# tennisfortwof303.net
KiCad netlist of a schematic drawn in EAGLE
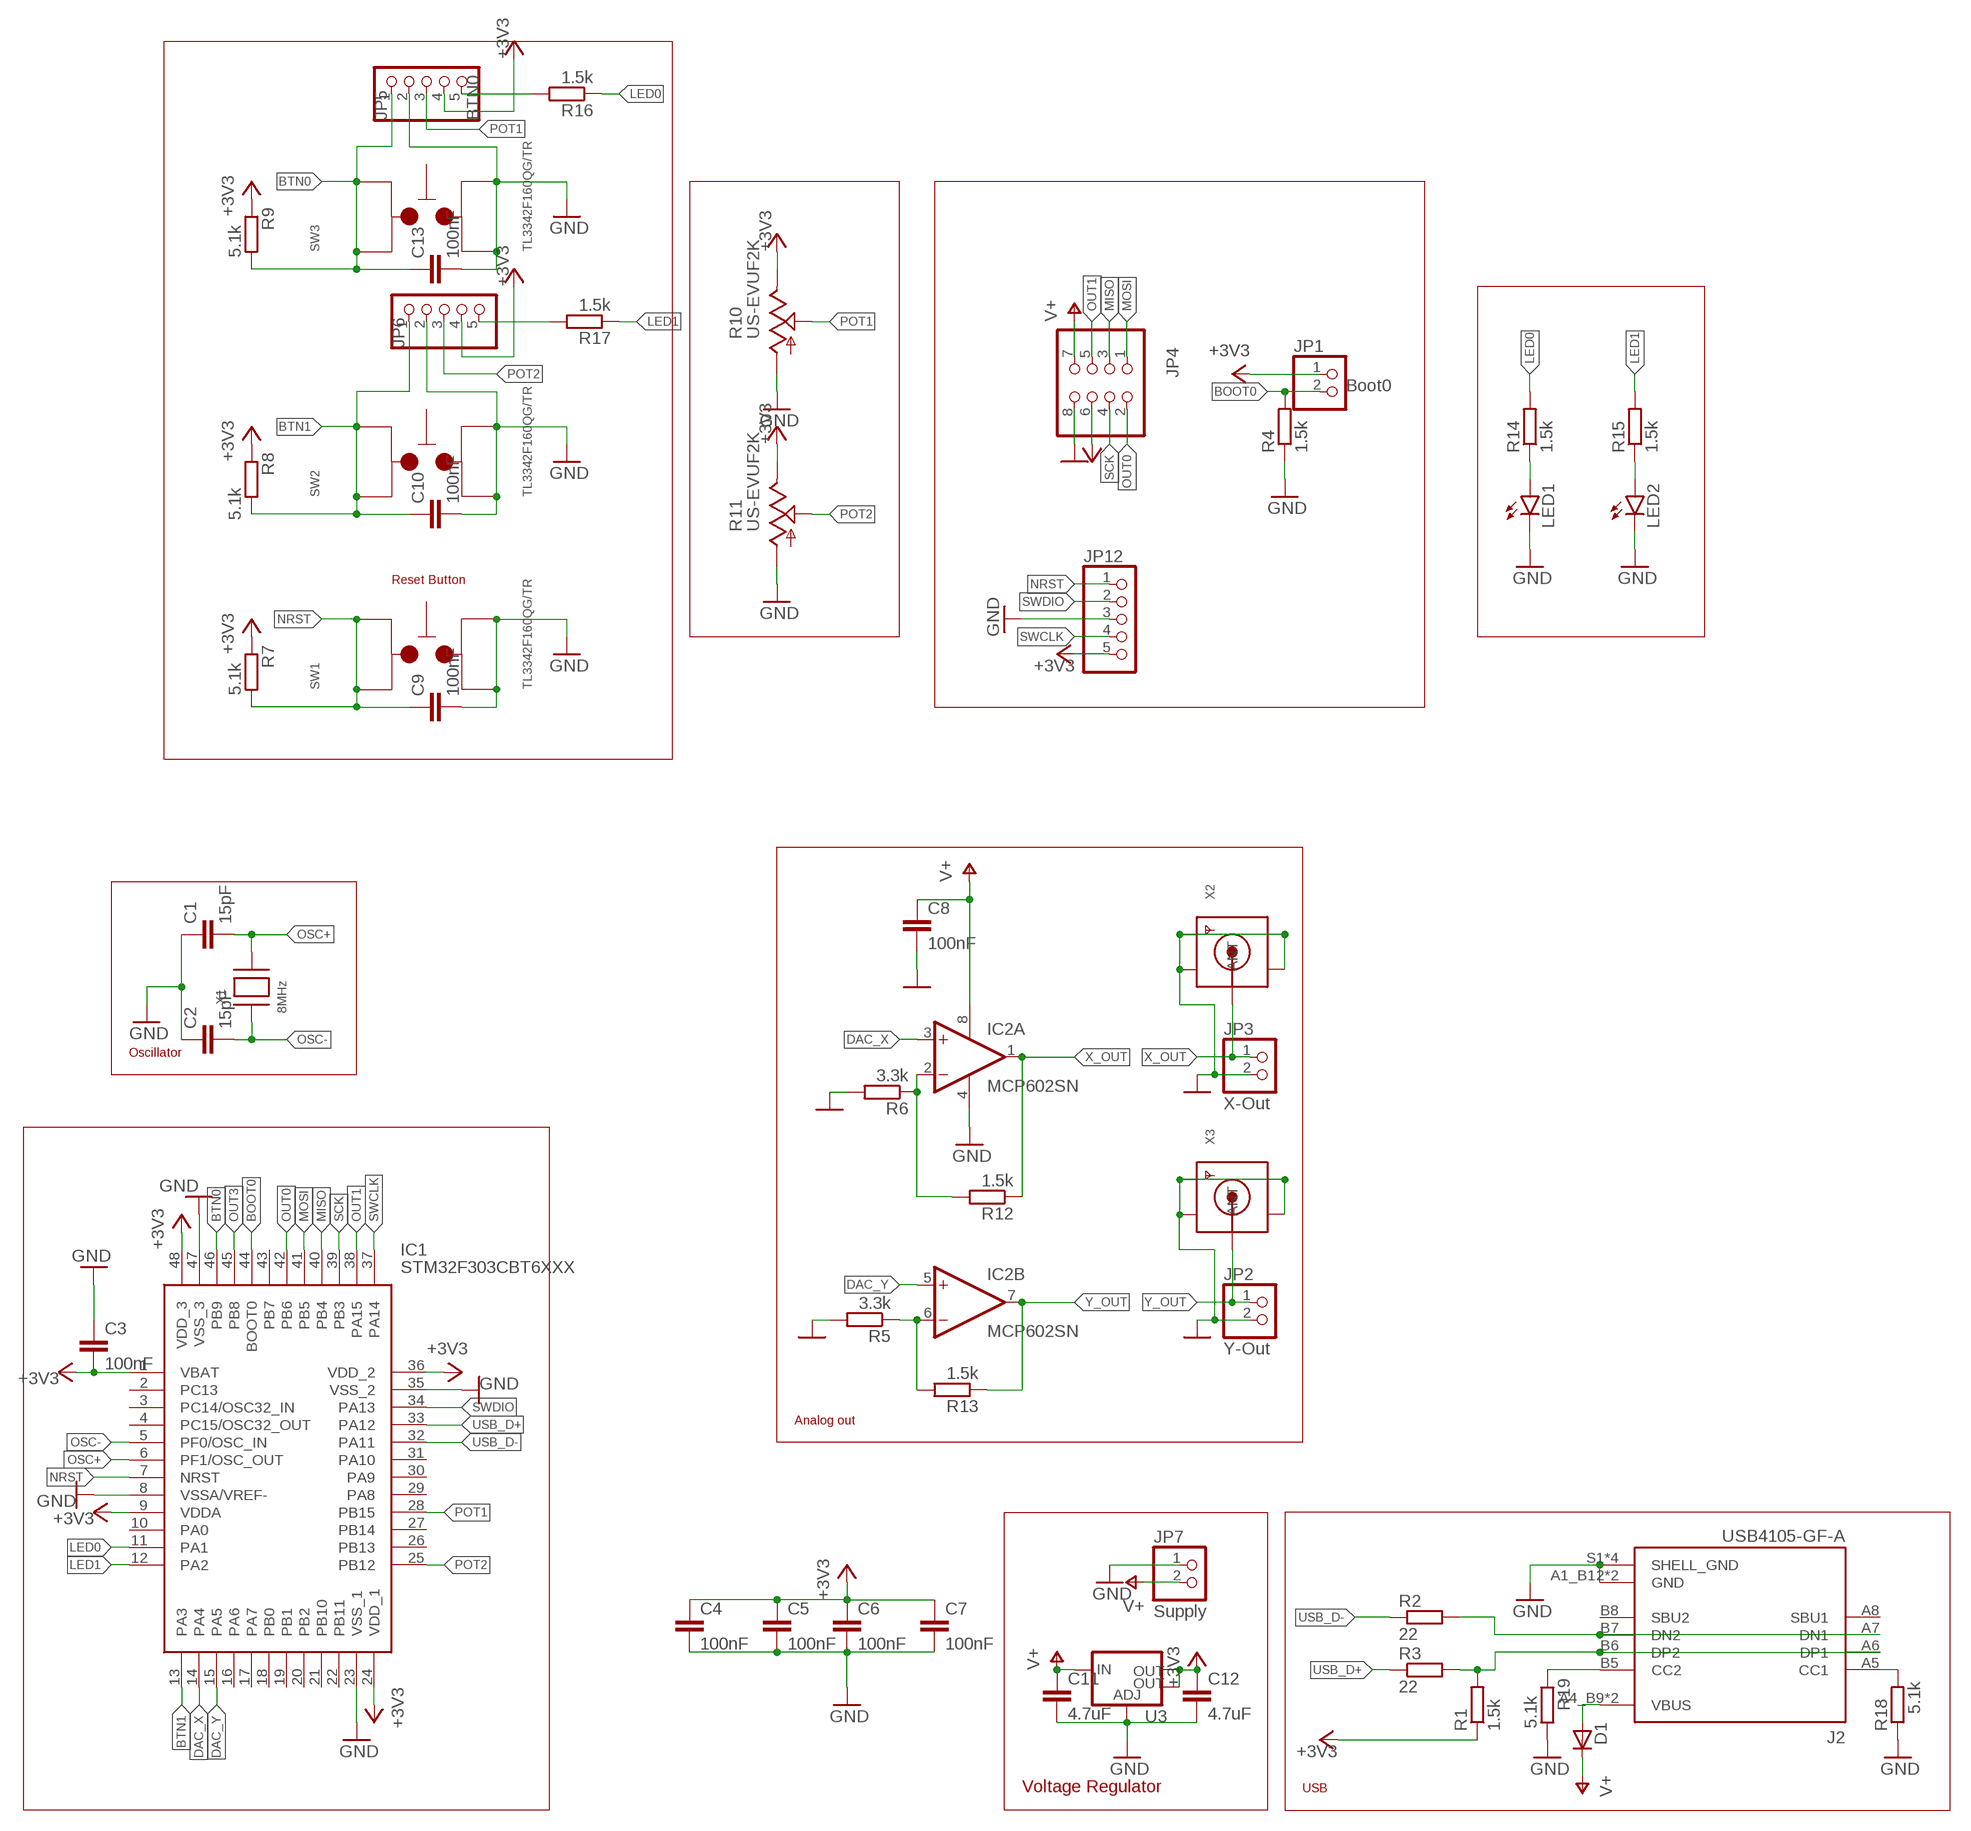
[diagram p0: schematic, sheet 1]

(export (version "E")
  (design (tool "Eeschema 10.0.6"))
  (components
    (comp (ref "C1")
      (value "15pF")
      (footprint "eagle-import:C0603")
      (libsource (lib "eagle-import") (part "C-EUC0603"))
    )
    (comp (ref "C2")
      (value "15pF")
      (footprint "eagle-import:C0603")
      (libsource (lib "eagle-import") (part "C-EUC0603"))
    )
    (comp (ref "C3")
      (value "100nF")
      (footprint "eagle-import:C0603")
      (libsource (lib "eagle-import") (part "C-EUC0603"))
    )
    (comp (ref "C4")
      (value "100nF")
      (footprint "eagle-import:C0603")
      (libsource (lib "eagle-import") (part "C-EUC0603"))
    )
    (comp (ref "C5")
      (value "100nF")
      (footprint "eagle-import:C0603")
      (libsource (lib "eagle-import") (part "C-EUC0603"))
    )
    (comp (ref "C6")
      (value "100nF")
      (footprint "eagle-import:C0603")
      (libsource (lib "eagle-import") (part "C-EUC0603"))
    )
    (comp (ref "C7")
      (value "100nF")
      (footprint "eagle-import:C0603")
      (libsource (lib "eagle-import") (part "C-EUC0603"))
    )
    (comp (ref "C8")
      (value "100nF")
      (footprint "eagle-import:C0603")
      (libsource (lib "eagle-import") (part "C-EUC0603"))
    )
    (comp (ref "C9")
      (value "100nF")
      (footprint "eagle-import:C0603")
      (libsource (lib "eagle-import") (part "C-EUC0603"))
    )
    (comp (ref "C10")
      (value "100nF")
      (footprint "eagle-import:C0603")
      (libsource (lib "eagle-import") (part "C-EUC0603"))
    )
    (comp (ref "C11")
      (value "4.7uF")
      (footprint "eagle-import:C0805")
      (libsource (lib "eagle-import") (part "C-EUC0805"))
    )
    (comp (ref "C12")
      (value "4.7uF")
      (footprint "eagle-import:C0805")
      (libsource (lib "eagle-import") (part "C-EUC0805"))
    )
    (comp (ref "C13")
      (value "100nF")
      (footprint "eagle-import:C0603")
      (libsource (lib "eagle-import") (part "C-EUC0603"))
    )
    (comp (ref "D1")
      (value "DIODESMA")
      (footprint "eagle-import:SMADIODE")
      (libsource (lib "eagle-import") (part "DIODESMA"))
    )
    (comp (ref "IC1")
      (value "STM32F303CBT6XXX")
      (footprint "eagle-import:QFP50P900X900X160-48N")
      (libsource (lib "eagle-import") (part "STM32F303CBT6XXX"))
    )
    (comp (ref "IC2")
      (value "MCP602SN")
      (footprint "eagle-import:SO08")
      (libsource (lib "eagle-import") (part "MCP602SN"))
    )
    (comp (ref "J2")
      (value "USB4105-GF-A")
      (footprint "eagle-import:GCT_USB4105-GF-A")
      (fields (field (name "MF") "GCT"))
      (libsource (lib "eagle-import") (part "USB4105-GF-A"))
    )
    (comp (ref "JP1")
      (value "Boot0")
      (footprint "eagle-import:1X02")
      (libsource (lib "eagle-import") (part "PINHD-1X2"))
    )
    (comp (ref "JP2")
      (value "Y-Out")
      (footprint "eagle-import:1X02")
      (libsource (lib "eagle-import") (part "PINHD-1X2"))
    )
    (comp (ref "JP3")
      (value "X-Out")
      (footprint "eagle-import:1X02")
      (libsource (lib "eagle-import") (part "PINHD-1X2"))
    )
    (comp (ref "JP4")
      (value "PINHD-2X4")
      (footprint "eagle-import:2X04")
      (libsource (lib "eagle-import") (part "PINHD-2X4"))
    )
    (comp (ref "JP5")
      (value "BTN0")
      (footprint "eagle-import:1X05_90")
      (libsource (lib "eagle-import") (part "PINHD-1X5/90"))
    )
    (comp (ref "JP6")
      (value "BTN1")
      (footprint "eagle-import:1X05_90")
      (libsource (lib "eagle-import") (part "PINHD-1X5/90"))
    )
    (comp (ref "JP7")
      (value "Supply")
      (footprint "eagle-import:1X02")
      (libsource (lib "eagle-import") (part "PINHD-1X2"))
    )
    (comp (ref "JP12")
      (value "PINHD-1X5")
      (footprint "eagle-import:1X05")
      (libsource (lib "eagle-import") (part "PINHD-1X5"))
    )
    (comp (ref "LED1")
      (value "LEDCHIPLED_0805")
      (footprint "eagle-import:CHIPLED_0805")
      (libsource (lib "eagle-import") (part "LEDCHIPLED_0805"))
    )
    (comp (ref "LED2")
      (value "LEDCHIPLED_0805")
      (footprint "eagle-import:CHIPLED_0805")
      (libsource (lib "eagle-import") (part "LEDCHIPLED_0805"))
    )
    (comp (ref "R1")
      (value "1.5k")
      (footprint "eagle-import:R0603")
      (libsource (lib "eagle-import") (part "R-EU_R0603"))
    )
    (comp (ref "R2")
      (value "22")
      (footprint "eagle-import:R0603")
      (libsource (lib "eagle-import") (part "R-EU_R0603"))
    )
    (comp (ref "R3")
      (value "22")
      (footprint "eagle-import:R0603")
      (libsource (lib "eagle-import") (part "R-EU_R0603"))
    )
    (comp (ref "R4")
      (value "1.5k")
      (footprint "eagle-import:R0603")
      (libsource (lib "eagle-import") (part "R-EU_R0603"))
    )
    (comp (ref "R5")
      (value "3.3k")
      (footprint "eagle-import:R0603")
      (libsource (lib "eagle-import") (part "R-EU_R0603"))
    )
    (comp (ref "R6")
      (value "3.3k")
      (footprint "eagle-import:R0603")
      (libsource (lib "eagle-import") (part "R-EU_R0603"))
    )
    (comp (ref "R7")
      (value "5.1k")
      (footprint "eagle-import:R0603")
      (libsource (lib "eagle-import") (part "R-EU_R0603"))
    )
    (comp (ref "R8")
      (value "5.1k")
      (footprint "eagle-import:R0603")
      (libsource (lib "eagle-import") (part "R-EU_R0603"))
    )
    (comp (ref "R9")
      (value "5.1k")
      (footprint "eagle-import:R0603")
      (libsource (lib "eagle-import") (part "R-EU_R0603"))
    )
    (comp (ref "R10")
      (value "US-EVUF2K")
      (footprint "eagle-import:EVUFXK")
      (libsource (lib "eagle-import") (part "US-EVUF2K"))
    )
    (comp (ref "R11")
      (value "US-EVUF2K")
      (footprint "eagle-import:EVUFXK")
      (libsource (lib "eagle-import") (part "US-EVUF2K"))
    )
    (comp (ref "R12")
      (value "1.5k")
      (footprint "eagle-import:R0603")
      (libsource (lib "eagle-import") (part "R-EU_R0603"))
    )
    (comp (ref "R13")
      (value "1.5k")
      (footprint "eagle-import:R0603")
      (libsource (lib "eagle-import") (part "R-EU_R0603"))
    )
    (comp (ref "R14")
      (value "1.5k")
      (footprint "eagle-import:R0603")
      (libsource (lib "eagle-import") (part "R-EU_R0603"))
    )
    (comp (ref "R15")
      (value "1.5k")
      (footprint "eagle-import:R0603")
      (libsource (lib "eagle-import") (part "R-EU_R0603"))
    )
    (comp (ref "R16")
      (value "1.5k")
      (footprint "eagle-import:R0603")
      (libsource (lib "eagle-import") (part "R-EU_R0603"))
    )
    (comp (ref "R17")
      (value "1.5k")
      (footprint "eagle-import:R0603")
      (libsource (lib "eagle-import") (part "R-EU_R0603"))
    )
    (comp (ref "R18")
      (value "5.1k")
      (footprint "eagle-import:R0603")
      (libsource (lib "eagle-import") (part "R-EU_R0603"))
    )
    (comp (ref "R19")
      (value "5.1k")
      (footprint "eagle-import:R0603")
      (libsource (lib "eagle-import") (part "R-EU_R0603"))
    )
    (comp (ref "SW1")
      (value "TL3342F160QG/TR")
      (footprint "eagle-import:TL3342F160QG_TR")
      (fields
        (field (name "DIGI_KEY_PART_NUMBER") "EG2531CT-ND")
        (field (name "MANUFACTURER") "E-Switch")
        (field (name "CREATED_BY") "PCBLayout.com")
      )
      (libsource (lib "eagle-import") (part "TL3342F160QG/TR"))
    )
    (comp (ref "SW2")
      (value "TL3342F160QG/TR")
      (footprint "eagle-import:TL3342F160QG_TR")
      (fields
        (field (name "DIGI_KEY_PART_NUMBER") "EG2531CT-ND")
        (field (name "MANUFACTURER") "E-Switch")
        (field (name "CREATED_BY") "PCBLayout.com")
      )
      (libsource (lib "eagle-import") (part "TL3342F160QG/TR"))
    )
    (comp (ref "SW3")
      (value "TL3342F160QG/TR")
      (footprint "eagle-import:TL3342F160QG_TR")
      (fields
        (field (name "DIGI_KEY_PART_NUMBER") "EG2531CT-ND")
        (field (name "MANUFACTURER") "E-Switch")
        (field (name "CREATED_BY") "PCBLayout.com")
      )
      (libsource (lib "eagle-import") (part "TL3342F160QG/TR"))
    )
    (comp (ref "U3")
      (value "V_REG_LM1117SOT223")
      (footprint "eagle-import:SOT223")
      (libsource (lib "eagle-import") (part "V_REG_LM1117SOT223"))
    )
    (comp (ref "X1")
      (value "8MHz")
      (footprint "eagle-import:NX5032")
      (libsource (lib "eagle-import") (part "XTALNX5032"))
    )
    (comp (ref "X2")
      (value "SMACONNECTOR_EDGE")
      (footprint "eagle-import:SMA_EDGELAUNCH")
      (libsource (lib "eagle-import") (part "SMACONNECTOR_EDGE"))
    )
    (comp (ref "X3")
      (value "SMACONNECTOR_EDGE")
      (footprint "eagle-import:SMA_EDGELAUNCH")
      (libsource (lib "eagle-import") (part "SMACONNECTOR_EDGE"))
    )
  )
  (nets
    (net (code "1") (name "+3V3") (class "Default")
      (node (ref "C12") (pin "1") (pinfunction "1_1") (pintype "passive"))
      (node (ref "C3") (pin "2") (pinfunction "2_2") (pintype "passive"))
      (node (ref "C4") (pin "1") (pinfunction "1_1") (pintype "passive"))
      (node (ref "C5") (pin "1") (pinfunction "1_1") (pintype "passive"))
      (node (ref "C6") (pin "1") (pinfunction "1_1") (pintype "passive"))
      (node (ref "C7") (pin "1") (pinfunction "1_1") (pintype "passive"))
      (node (ref "IC1") (pin "1") (pinfunction "VBAT_1") (pintype "bidirectional"))
      (node (ref "IC1") (pin "24") (pinfunction "VDD_1_24") (pintype "bidirectional"))
      (node (ref "IC1") (pin "36") (pinfunction "VDD_2_36") (pintype "bidirectional"))
      (node (ref "IC1") (pin "48") (pinfunction "VDD_3_48") (pintype "bidirectional"))
      (node (ref "IC1") (pin "9") (pinfunction "VDDA_9") (pintype "bidirectional"))
      (node (ref "JP1") (pin "1") (pinfunction "1_1") (pintype "passive"))
      (node (ref "JP12") (pin "5") (pinfunction "5_5") (pintype "passive"))
      (node (ref "JP4") (pin "6") (pinfunction "6_6") (pintype "passive"))
      (node (ref "JP5") (pin "4") (pinfunction "4_4") (pintype "passive"))
      (node (ref "JP6") (pin "4") (pinfunction "4_4") (pintype "passive"))
      (node (ref "R1") (pin "1") (pinfunction "1_1") (pintype "passive"))
      (node (ref "R10") (pin "3") (pinfunction "E_3") (pintype "passive"))
      (node (ref "R11") (pin "3") (pinfunction "E_3") (pintype "passive"))
      (node (ref "R7") (pin "1") (pinfunction "1_1") (pintype "passive"))
      (node (ref "R8") (pin "1") (pinfunction "1_1") (pintype "passive"))
      (node (ref "R9") (pin "1") (pinfunction "1_1") (pintype "passive"))
      (node (ref "U3") (pin "2") (pinfunction "OUT_2") (pintype "output"))
      (node (ref "U3") (pin "4") (pinfunction "OUT_4") (pintype "output"))
    )
    (net (code "2") (name "BOOT0") (class "Default")
      (node (ref "IC1") (pin "44") (pinfunction "BOOT0_44") (pintype "bidirectional"))
      (node (ref "JP1") (pin "2") (pinfunction "2_2") (pintype "passive"))
      (node (ref "R4") (pin "2") (pinfunction "2_2") (pintype "passive"))
    )
    (net (code "3") (name "BTN0") (class "Default")
      (node (ref "C13") (pin "1") (pinfunction "1_1") (pintype "passive"))
      (node (ref "IC1") (pin "46") (pinfunction "PB9_46") (pintype "bidirectional"))
      (node (ref "JP5") (pin "1") (pinfunction "1_1") (pintype "passive"))
      (node (ref "R9") (pin "2") (pinfunction "2_2") (pintype "passive"))
      (node (ref "SW3") (pin "3") (pinfunction "3_3") (pintype "passive"))
      (node (ref "SW3") (pin "4") (pinfunction "4_4") (pintype "passive"))
    )
    (net (code "4") (name "BTN1") (class "Default")
      (node (ref "C10") (pin "1") (pinfunction "1_1") (pintype "passive"))
      (node (ref "IC1") (pin "13") (pinfunction "PA3_13") (pintype "bidirectional"))
      (node (ref "JP6") (pin "1") (pinfunction "1_1") (pintype "passive"))
      (node (ref "R8") (pin "2") (pinfunction "2_2") (pintype "passive"))
      (node (ref "SW2") (pin "3") (pinfunction "3_3") (pintype "passive"))
      (node (ref "SW2") (pin "4") (pinfunction "4_4") (pintype "passive"))
    )
    (net (code "5") (name "DAC_X") (class "Default")
      (node (ref "IC1") (pin "14") (pinfunction "PA4_14") (pintype "bidirectional"))
      (node (ref "IC2") (pin "3") (pinfunction "+IN_3") (pintype "input"))
    )
    (net (code "6") (name "DAC_Y") (class "Default")
      (node (ref "IC1") (pin "15") (pinfunction "PA5_15") (pintype "bidirectional"))
      (node (ref "IC2") (pin "5") (pinfunction "+IN_5") (pintype "input"))
    )
    (net (code "7") (name "GND") (class "Default")
      (node (ref "C1") (pin "1") (pinfunction "1_1") (pintype "passive"))
      (node (ref "C10") (pin "2") (pinfunction "2_2") (pintype "passive"))
      (node (ref "C11") (pin "2") (pinfunction "2_2") (pintype "passive"))
      (node (ref "C12") (pin "2") (pinfunction "2_2") (pintype "passive"))
      (node (ref "C13") (pin "2") (pinfunction "2_2") (pintype "passive"))
      (node (ref "C2") (pin "1") (pinfunction "1_1") (pintype "passive"))
      (node (ref "C3") (pin "1") (pinfunction "1_1") (pintype "passive"))
      (node (ref "C4") (pin "2") (pinfunction "2_2") (pintype "passive"))
      (node (ref "C5") (pin "2") (pinfunction "2_2") (pintype "passive"))
      (node (ref "C6") (pin "2") (pinfunction "2_2") (pintype "passive"))
      (node (ref "C7") (pin "2") (pinfunction "2_2") (pintype "passive"))
      (node (ref "C8") (pin "2") (pinfunction "2_2") (pintype "passive"))
      (node (ref "C9") (pin "2") (pinfunction "2_2") (pintype "passive"))
      (node (ref "IC1") (pin "23") (pinfunction "VSS_1_23") (pintype "bidirectional"))
      (node (ref "IC1") (pin "35") (pinfunction "VSS_2_35") (pintype "bidirectional"))
      (node (ref "IC1") (pin "47") (pinfunction "VSS_3_47") (pintype "bidirectional"))
      (node (ref "IC1") (pin "8") (pinfunction "VSSA/VREF-_8") (pintype "bidirectional"))
      (node (ref "IC2") (pin "4") (pinfunction "V-_4") (pintype "power_in"))
      (node (ref "J2") (pin "A1_B12") (pinfunction "GND_A1_B12") (pintype "power_in"))
      (node (ref "J2") (pin "B1_A12") (pinfunction "GND_B1_A12") (pintype "power_in"))
      (node (ref "J2") (pin "S1") (pinfunction "SHELL_GND_S1") (pintype "power_in"))
      (node (ref "J2") (pin "S2") (pinfunction "SHELL_GND_S2") (pintype "power_in"))
      (node (ref "J2") (pin "S3") (pinfunction "SHELL_GND_S3") (pintype "power_in"))
      (node (ref "J2") (pin "S4") (pinfunction "SHELL_GND_S4") (pintype "power_in"))
      (node (ref "JP12") (pin "3") (pinfunction "3_3") (pintype "passive"))
      (node (ref "JP2") (pin "2") (pinfunction "2_2") (pintype "passive"))
      (node (ref "JP3") (pin "2") (pinfunction "2_2") (pintype "passive"))
      (node (ref "JP4") (pin "8") (pinfunction "8_8") (pintype "passive"))
      (node (ref "JP5") (pin "2") (pinfunction "2_2") (pintype "passive"))
      (node (ref "JP6") (pin "2") (pinfunction "2_2") (pintype "passive"))
      (node (ref "JP7") (pin "1") (pinfunction "1_1") (pintype "passive"))
      (node (ref "LED1") (pin "C") (pinfunction "C_C") (pintype "passive"))
      (node (ref "LED2") (pin "C") (pinfunction "C_C") (pintype "passive"))
      (node (ref "R10") (pin "1") (pinfunction "A_1") (pintype "passive"))
      (node (ref "R11") (pin "1") (pinfunction "A_1") (pintype "passive"))
      (node (ref "R18") (pin "1") (pinfunction "1_1") (pintype "passive"))
      (node (ref "R19") (pin "2") (pinfunction "2_2") (pintype "passive"))
      (node (ref "R4") (pin "1") (pinfunction "1_1") (pintype "passive"))
      (node (ref "R5") (pin "2") (pinfunction "2_2") (pintype "passive"))
      (node (ref "R6") (pin "2") (pinfunction "2_2") (pintype "passive"))
      (node (ref "SW1") (pin "1") (pinfunction "1_1") (pintype "passive"))
      (node (ref "SW1") (pin "2") (pinfunction "2_2") (pintype "passive"))
      (node (ref "SW2") (pin "1") (pinfunction "1_1") (pintype "passive"))
      (node (ref "SW2") (pin "2") (pinfunction "2_2") (pintype "passive"))
      (node (ref "SW3") (pin "1") (pinfunction "1_1") (pintype "passive"))
      (node (ref "SW3") (pin "2") (pinfunction "2_2") (pintype "passive"))
      (node (ref "U3") (pin "1") (pinfunction "ADJ_1") (pintype "input"))
      (node (ref "X2") (pin "GND@1") (pinfunction "GND4_GND@1") (pintype "power_in"))
      (node (ref "X2") (pin "GND@2") (pinfunction "GND3_GND@2") (pintype "power_in"))
      (node (ref "X2") (pin "GND@3") (pinfunction "GND2_GND@3") (pintype "power_in"))
      (node (ref "X2") (pin "GND@4") (pinfunction "GND1_GND@4") (pintype "power_in"))
      (node (ref "X3") (pin "GND@1") (pinfunction "GND4_GND@1") (pintype "power_in"))
      (node (ref "X3") (pin "GND@2") (pinfunction "GND3_GND@2") (pintype "power_in"))
      (node (ref "X3") (pin "GND@3") (pinfunction "GND2_GND@3") (pintype "power_in"))
      (node (ref "X3") (pin "GND@4") (pinfunction "GND1_GND@4") (pintype "power_in"))
    )
    (net (code "8") (name "LED0") (class "Default")
      (node (ref "IC1") (pin "11") (pinfunction "PA1_11") (pintype "bidirectional"))
      (node (ref "R14") (pin "2") (pinfunction "2_2") (pintype "passive"))
      (node (ref "R16") (pin "1") (pinfunction "1_1") (pintype "passive"))
    )
    (net (code "9") (name "LED1") (class "Default")
      (node (ref "IC1") (pin "12") (pinfunction "PA2_12") (pintype "bidirectional"))
      (node (ref "R15") (pin "2") (pinfunction "2_2") (pintype "passive"))
      (node (ref "R17") (pin "1") (pinfunction "1_1") (pintype "passive"))
    )
    (net (code "10") (name "MISO") (class "Default")
      (node (ref "IC1") (pin "40") (pinfunction "PB4_40") (pintype "bidirectional"))
      (node (ref "JP4") (pin "3") (pinfunction "3_3") (pintype "passive"))
    )
    (net (code "11") (name "MOSI") (class "Default")
      (node (ref "IC1") (pin "41") (pinfunction "PB5_41") (pintype "bidirectional"))
      (node (ref "JP4") (pin "1") (pinfunction "1_1") (pintype "passive"))
    )
    (net (code "12") (name "NRST") (class "Default")
      (node (ref "C9") (pin "1") (pinfunction "1_1") (pintype "passive"))
      (node (ref "IC1") (pin "7") (pinfunction "NRST_7") (pintype "bidirectional"))
      (node (ref "JP12") (pin "1") (pinfunction "1_1") (pintype "passive"))
      (node (ref "R7") (pin "2") (pinfunction "2_2") (pintype "passive"))
      (node (ref "SW1") (pin "3") (pinfunction "3_3") (pintype "passive"))
      (node (ref "SW1") (pin "4") (pinfunction "4_4") (pintype "passive"))
    )
    (net (code "13") (name "Net-(D1-PadA)") (class "Default")
      (node (ref "D1") (pin "A") (pinfunction "A_A") (pintype "passive"))
      (node (ref "J2") (pin "A4_B9") (pinfunction "VBUS_A4_B9") (pintype "power_in"))
      (node (ref "J2") (pin "B4_A9") (pinfunction "VBUS_B4_A9") (pintype "power_in"))
    )
    (net (code "14") (name "Net-(IC2A--IN)") (class "Default")
      (node (ref "IC2") (pin "2") (pinfunction "-IN_2") (pintype "input"))
      (node (ref "R12") (pin "2") (pinfunction "2_2") (pintype "passive"))
      (node (ref "R6") (pin "1") (pinfunction "1_1") (pintype "passive"))
    )
    (net (code "15") (name "Net-(IC2B--IN)") (class "Default")
      (node (ref "IC2") (pin "6") (pinfunction "-IN_6") (pintype "input"))
      (node (ref "R13") (pin "2") (pinfunction "2_2") (pintype "passive"))
      (node (ref "R5") (pin "1") (pinfunction "1_1") (pintype "passive"))
    )
    (net (code "16") (name "Net-(J2-CC1)") (class "Default")
      (node (ref "J2") (pin "A5") (pinfunction "CC1_A5") (pintype "bidirectional"))
      (node (ref "R18") (pin "2") (pinfunction "2_2") (pintype "passive"))
    )
    (net (code "17") (name "Net-(J2-CC2)") (class "Default")
      (node (ref "J2") (pin "B5") (pinfunction "CC2_B5") (pintype "bidirectional"))
      (node (ref "R19") (pin "1") (pinfunction "1_1") (pintype "passive"))
    )
    (net (code "18") (name "Net-(J2-DN1)") (class "Default")
      (node (ref "J2") (pin "A7") (pinfunction "DN1_A7") (pintype "bidirectional"))
      (node (ref "J2") (pin "B7") (pinfunction "DN2_B7") (pintype "bidirectional"))
      (node (ref "R2") (pin "2") (pinfunction "2_2") (pintype "passive"))
    )
    (net (code "19") (name "Net-(J2-DP1)") (class "Default")
      (node (ref "J2") (pin "A6") (pinfunction "DP1_A6") (pintype "bidirectional"))
      (node (ref "J2") (pin "B6") (pinfunction "DP2_B6") (pintype "bidirectional"))
      (node (ref "R1") (pin "2") (pinfunction "2_2") (pintype "passive"))
      (node (ref "R3") (pin "2") (pinfunction "2_2") (pintype "passive"))
    )
    (net (code "20") (name "Net-(JP5-Pad5)") (class "Default")
      (node (ref "JP5") (pin "5") (pinfunction "5_5") (pintype "passive"))
      (node (ref "R16") (pin "2") (pinfunction "2_2") (pintype "passive"))
    )
    (net (code "21") (name "Net-(JP6-Pad5)") (class "Default")
      (node (ref "JP6") (pin "5") (pinfunction "5_5") (pintype "passive"))
      (node (ref "R17") (pin "2") (pinfunction "2_2") (pintype "passive"))
    )
    (net (code "22") (name "Net-(LED1-PadA)") (class "Default")
      (node (ref "LED1") (pin "A") (pinfunction "A_A") (pintype "passive"))
      (node (ref "R14") (pin "1") (pinfunction "1_1") (pintype "passive"))
    )
    (net (code "23") (name "Net-(LED2-PadA)") (class "Default")
      (node (ref "LED2") (pin "A") (pinfunction "A_A") (pintype "passive"))
      (node (ref "R15") (pin "1") (pinfunction "1_1") (pintype "passive"))
    )
    (net (code "24") (name "OSC+") (class "Default")
      (node (ref "C1") (pin "2") (pinfunction "2_2") (pintype "passive"))
      (node (ref "IC1") (pin "6") (pinfunction "PF1/OSC_OUT_6") (pintype "bidirectional"))
      (node (ref "X1") (pin "P$2") (pinfunction "P$2_P$2") (pintype "bidirectional"))
    )
    (net (code "25") (name "OSC-") (class "Default")
      (node (ref "C2") (pin "2") (pinfunction "2_2") (pintype "passive"))
      (node (ref "IC1") (pin "5") (pinfunction "PF0/OSC_IN_5") (pintype "bidirectional"))
      (node (ref "X1") (pin "P$1") (pinfunction "P$1_P$1") (pintype "bidirectional"))
    )
    (net (code "26") (name "OUT0") (class "Default")
      (node (ref "IC1") (pin "42") (pinfunction "PB6_42") (pintype "bidirectional"))
      (node (ref "JP4") (pin "2") (pinfunction "2_2") (pintype "passive"))
    )
    (net (code "27") (name "OUT1") (class "Default")
      (node (ref "IC1") (pin "38") (pinfunction "PA15_38") (pintype "bidirectional"))
      (node (ref "JP4") (pin "5") (pinfunction "5_5") (pintype "passive"))
    )
    (net (code "28") (name "OUT3") (class "Default")
      (node (ref "IC1") (pin "45") (pinfunction "PB8_45") (pintype "bidirectional"))
    )
    (net (code "29") (name "POT1") (class "Default")
      (node (ref "IC1") (pin "28") (pinfunction "PB15_28") (pintype "bidirectional"))
      (node (ref "JP5") (pin "3") (pinfunction "3_3") (pintype "passive"))
      (node (ref "R10") (pin "2") (pinfunction "S_2") (pintype "passive"))
    )
    (net (code "30") (name "POT2") (class "Default")
      (node (ref "IC1") (pin "25") (pinfunction "PB12_25") (pintype "bidirectional"))
      (node (ref "JP6") (pin "3") (pinfunction "3_3") (pintype "passive"))
      (node (ref "R11") (pin "2") (pinfunction "S_2") (pintype "passive"))
    )
    (net (code "31") (name "SCK") (class "Default")
      (node (ref "IC1") (pin "39") (pinfunction "PB3_39") (pintype "bidirectional"))
      (node (ref "JP4") (pin "4") (pinfunction "4_4") (pintype "passive"))
    )
    (net (code "32") (name "SWCLK") (class "Default")
      (node (ref "IC1") (pin "37") (pinfunction "PA14_37") (pintype "bidirectional"))
      (node (ref "JP12") (pin "4") (pinfunction "4_4") (pintype "passive"))
    )
    (net (code "33") (name "SWDIO") (class "Default")
      (node (ref "IC1") (pin "34") (pinfunction "PA13_34") (pintype "bidirectional"))
      (node (ref "JP12") (pin "2") (pinfunction "2_2") (pintype "passive"))
    )
    (net (code "34") (name "USB_D+") (class "Default")
      (node (ref "IC1") (pin "33") (pinfunction "PA12_33") (pintype "bidirectional"))
      (node (ref "R3") (pin "1") (pinfunction "1_1") (pintype "passive"))
    )
    (net (code "35") (name "USB_D-") (class "Default")
      (node (ref "IC1") (pin "32") (pinfunction "PA11_32") (pintype "bidirectional"))
      (node (ref "R2") (pin "1") (pinfunction "1_1") (pintype "passive"))
    )
    (net (code "36") (name "V+") (class "Default")
      (node (ref "C11") (pin "1") (pinfunction "1_1") (pintype "passive"))
      (node (ref "C8") (pin "1") (pinfunction "1_1") (pintype "passive"))
      (node (ref "D1") (pin "C") (pinfunction "C_C") (pintype "passive"))
      (node (ref "IC2") (pin "8") (pinfunction "V+_8") (pintype "power_in"))
      (node (ref "JP4") (pin "7") (pinfunction "7_7") (pintype "passive"))
      (node (ref "JP7") (pin "2") (pinfunction "2_2") (pintype "passive"))
      (node (ref "U3") (pin "3") (pinfunction "IN_3") (pintype "input"))
    )
    (net (code "37") (name "X_OUT") (class "Default")
      (node (ref "IC2") (pin "1") (pinfunction "OUT_1") (pintype "output"))
      (node (ref "JP3") (pin "1") (pinfunction "1_1") (pintype "passive"))
      (node (ref "R12") (pin "1") (pinfunction "1_1") (pintype "passive"))
      (node (ref "X2") (pin "P") (pinfunction "ANT_P") (pintype "bidirectional"))
    )
    (net (code "38") (name "Y_OUT") (class "Default")
      (node (ref "IC2") (pin "7") (pinfunction "OUT_7") (pintype "output"))
      (node (ref "JP2") (pin "1") (pinfunction "1_1") (pintype "passive"))
      (node (ref "R13") (pin "1") (pinfunction "1_1") (pintype "passive"))
      (node (ref "X3") (pin "P") (pinfunction "ANT_P") (pintype "bidirectional"))
    )
    (net (code "39") (name "unconnected-(IC1-PA0-Pad10)") (class "Default")
      (node (ref "IC1") (pin "10") (pinfunction "PA0_10") (pintype "bidirectional"))
    )
    (net (code "40") (name "unconnected-(IC1-PA6-Pad16)") (class "Default")
      (node (ref "IC1") (pin "16") (pinfunction "PA6_16") (pintype "bidirectional"))
    )
    (net (code "41") (name "unconnected-(IC1-PA7-Pad17)") (class "Default")
      (node (ref "IC1") (pin "17") (pinfunction "PA7_17") (pintype "bidirectional"))
    )
    (net (code "42") (name "unconnected-(IC1-PA8-Pad29)") (class "Default")
      (node (ref "IC1") (pin "29") (pinfunction "PA8_29") (pintype "bidirectional"))
    )
    (net (code "43") (name "unconnected-(IC1-PA9-Pad30)") (class "Default")
      (node (ref "IC1") (pin "30") (pinfunction "PA9_30") (pintype "bidirectional"))
    )
    (net (code "44") (name "unconnected-(IC1-PA10-Pad31)") (class "Default")
      (node (ref "IC1") (pin "31") (pinfunction "PA10_31") (pintype "bidirectional"))
    )
    (net (code "45") (name "unconnected-(IC1-PB0-Pad18)") (class "Default")
      (node (ref "IC1") (pin "18") (pinfunction "PB0_18") (pintype "bidirectional"))
    )
    (net (code "46") (name "unconnected-(IC1-PB1-Pad19)") (class "Default")
      (node (ref "IC1") (pin "19") (pinfunction "PB1_19") (pintype "bidirectional"))
    )
    (net (code "47") (name "unconnected-(IC1-PB2-Pad20)") (class "Default")
      (node (ref "IC1") (pin "20") (pinfunction "PB2_20") (pintype "bidirectional"))
    )
    (net (code "48") (name "unconnected-(IC1-PB7-Pad43)") (class "Default")
      (node (ref "IC1") (pin "43") (pinfunction "PB7_43") (pintype "bidirectional"))
    )
    (net (code "49") (name "unconnected-(IC1-PB10-Pad21)") (class "Default")
      (node (ref "IC1") (pin "21") (pinfunction "PB10_21") (pintype "bidirectional"))
    )
    (net (code "50") (name "unconnected-(IC1-PB11-Pad22)") (class "Default")
      (node (ref "IC1") (pin "22") (pinfunction "PB11_22") (pintype "bidirectional"))
    )
    (net (code "51") (name "unconnected-(IC1-PB13-Pad26)") (class "Default")
      (node (ref "IC1") (pin "26") (pinfunction "PB13_26") (pintype "bidirectional"))
    )
    (net (code "52") (name "unconnected-(IC1-PB14-Pad27)") (class "Default")
      (node (ref "IC1") (pin "27") (pinfunction "PB14_27") (pintype "bidirectional"))
    )
    (net (code "53") (name "unconnected-(IC1-PC13-Pad2)") (class "Default")
      (node (ref "IC1") (pin "2") (pinfunction "PC13_2") (pintype "bidirectional"))
    )
    (net (code "54") (name "unconnected-(IC1-PC14{slash}OSC32_IN-Pad3)") (class "Default")
      (node (ref "IC1") (pin "3") (pinfunction "PC14/OSC32_IN_3") (pintype "bidirectional"))
    )
    (net (code "55") (name "unconnected-(IC1-PC15{slash}OSC32_OUT-Pad4)") (class "Default")
      (node (ref "IC1") (pin "4") (pinfunction "PC15/OSC32_OUT_4") (pintype "bidirectional"))
    )
    (net (code "56") (name "unconnected-(J2-SBU1-PadA8)") (class "Default")
      (node (ref "J2") (pin "A8") (pinfunction "SBU1_A8") (pintype "bidirectional"))
    )
    (net (code "57") (name "unconnected-(J2-SBU2-PadB8)") (class "Default")
      (node (ref "J2") (pin "B8") (pinfunction "SBU2_B8") (pintype "bidirectional"))
    )
  )
)
